# PongBoy.net
KiCad netlist of a schematic drawn in Altium Designer
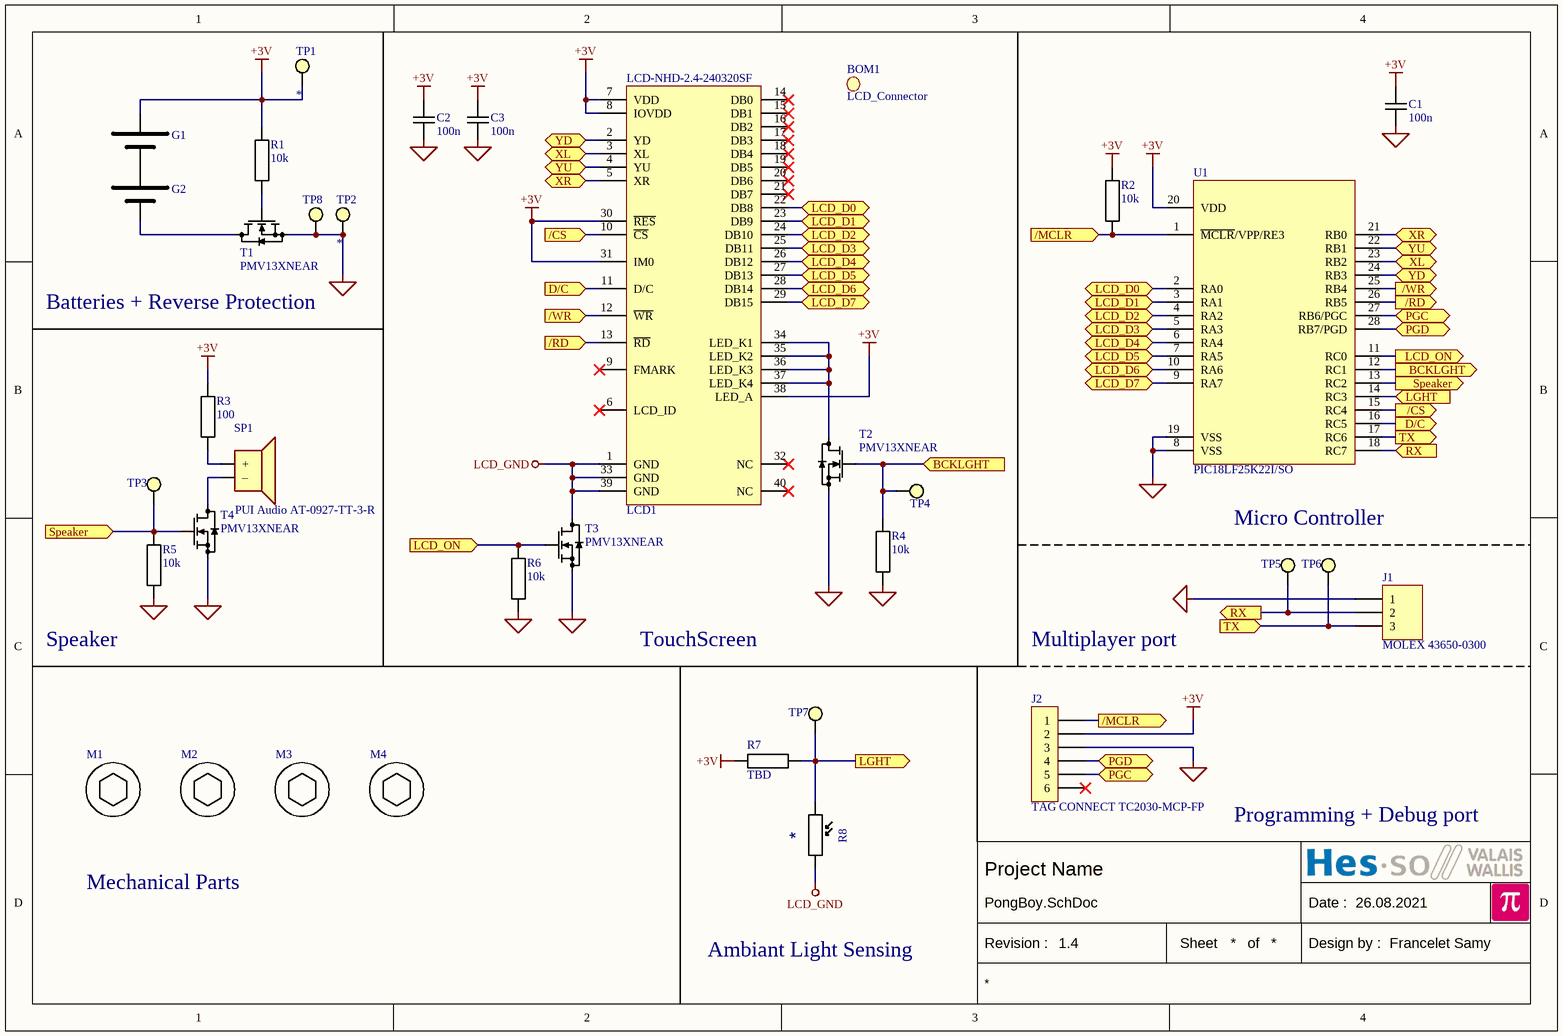
[diagram p0: PongBoy.SchDoc]

(export (version "E")
  (design (tool "Eeschema 10.0.6"))
  (components
    (comp (ref "BOM1")
      (value "LCD_Connector")
      (description "Component without pattern")
      (libsource (lib "altium-import") (part "root_0_Additional BOM Entry_"))
    )
    (comp (ref "C1")
      (value "100n")
      (footprint "CAPACITOR 2012 REFLOW")
      (description "Capacitor")
      (libsource (lib "altium-import") (part "root_1_Capacitor_"))
    )
    (comp (ref "C2")
      (value "100n")
      (footprint "CAPACITOR 2012 REFLOW")
      (description "Capacitor")
      (libsource (lib "altium-import") (part "root_1_Capacitor_"))
    )
    (comp (ref "C3")
      (value "100n")
      (footprint "CAPACITOR 2012 REFLOW")
      (description "Capacitor")
      (libsource (lib "altium-import") (part "root_1_Capacitor_"))
    )
    (comp (ref "G1")
      (value "AAA Battery Holder")
      (footprint "1.5V Cell AAA/LR03")
      (description "Battery Generic")
      (libsource (lib "altium-import") (part "root_0_Battery_"))
    )
    (comp (ref "G2")
      (value "AAA Battery Holder")
      (footprint "1.5V Cell AAA/LR03")
      (description "Battery Generic")
      (libsource (lib "altium-import") (part "root_0_Battery_"))
    )
    (comp (ref "J1")
      (value "MOLEX 43650-0300")
      (footprint "MOLEX 43650-0300")
      (description "Micro-Fit 3.0 Right-Angle Header, 3.00mm Pitch, Single Row, 3 Circuits")
      (libsource (lib "altium-import") (part "root_0_MOLEX 43650-0300_"))
    )
    (comp (ref "J2")
      (value "TAG CONNECT TC2030-MCP-FP")
      (footprint "TAG CONNECT TC2030-MCP-FP")
      (libsource (lib "altium-import") (part "root_0_mirrored_TAG CONNECT TC2030-MCP-FP_"))
    )
    (comp (ref "LCD1")
      (value "LCD-NHD-2.4-240320SF")
      (footprint "LCD-NHD-2.4-240320SF")
      (description "NEWHEAVEN LCD")
      (libsource (lib "altium-import") (part "root_0_LCD-NHD-2.4-240320SF_"))
    )
    (comp (ref "M1")
      (value "M3x20")
      (footprint "Screw Hex Socket M3X5 Unconnected")
      (description "Screw Hex Socket Unconnected BN610")
      (libsource (lib "altium-import") (part "root_0_Screw Hex Socket Unconnected_"))
    )
    (comp (ref "M2")
      (value "M3x20")
      (footprint "Screw Hex Socket M3X5 Unconnected")
      (description "Screw Hex Socket Unconnected BN610")
      (libsource (lib "altium-import") (part "root_0_Screw Hex Socket Unconnected_"))
    )
    (comp (ref "M3")
      (value "M3x20")
      (footprint "Screw Hex Socket M3X5 Unconnected")
      (description "Screw Hex Socket Unconnected BN610")
      (libsource (lib "altium-import") (part "root_0_Screw Hex Socket Unconnected_"))
    )
    (comp (ref "M4")
      (value "M3x20")
      (footprint "Screw Hex Socket M3X5 Unconnected")
      (description "Screw Hex Socket Unconnected BN610")
      (libsource (lib "altium-import") (part "root_0_Screw Hex Socket Unconnected_"))
    )
    (comp (ref "R1")
      (value "10k")
      (footprint "RESISTOR 2012 REFLOW")
      (description "Resistor")
      (libsource (lib "altium-import") (part "root_1_Resistor_"))
    )
    (comp (ref "R2")
      (value "10k")
      (footprint "RESISTOR 2012 REFLOW")
      (description "Resistor")
      (libsource (lib "altium-import") (part "root_1_Resistor_"))
    )
    (comp (ref "R3")
      (value "100")
      (footprint "RESISTOR 2012 REFLOW")
      (description "Resistor")
      (libsource (lib "altium-import") (part "root_1_Resistor_"))
    )
    (comp (ref "R4")
      (value "10k")
      (footprint "RESISTOR 2012 REFLOW")
      (description "Resistor")
      (libsource (lib "altium-import") (part "root_1_Resistor_"))
    )
    (comp (ref "R5")
      (value "10k")
      (footprint "RESISTOR 2012 REFLOW")
      (description "Resistor")
      (libsource (lib "altium-import") (part "root_1_Resistor_"))
    )
    (comp (ref "R6")
      (value "10k")
      (footprint "RESISTOR 2012 REFLOW")
      (description "Resistor")
      (libsource (lib "altium-import") (part "root_1_Resistor_"))
    )
    (comp (ref "R7")
      (value "TBD")
      (footprint "RESISTOR 2012 REFLOW")
      (description "Resistor")
      (libsource (lib "altium-import") (part "root_2_Resistor_"))
    )
    (comp (ref "R8")
      (value "*")
      (footprint "LDR VT900")
      (description "Light Dependent Resistor")
      (fields (field (name "ALTIUM_VALUE") "*"))
      (libsource (lib "altium-import") (part "root_3_LDR_"))
    )
    (comp (ref "SP1")
      (value "PUI Audio AT-0927-TT-3-R")
      (footprint "Speaker PUI Audio AT-0927-TT-3-R")
      (description "Speaker PUI Audio AT-0927-TT-3-R")
      (libsource (lib "altium-import") (part "root_0_Speaker PUI Audio AT-0927-TT-3-R_"))
    )
    (comp (ref "T1")
      (value "PMV13XNEAR")
      (footprint "SOT23 P0.95 C1.6x3.0 H1.3")
      (description "Generic MOS-N")
      (libsource (lib "altium-import") (part "root_3_mirrored_MOS-N SOT23 G-S-D_"))
    )
    (comp (ref "T2")
      (value "PMV13XNEAR")
      (footprint "SOT23 P0.95 C1.6x3.0 H1.3")
      (description "Generic MOS-N")
      (libsource (lib "altium-import") (part "root_0_mirrored_MOS-N SOT23 G-S-D_"))
    )
    (comp (ref "T3")
      (value "PMV13XNEAR")
      (footprint "SOT23 P0.95 C1.6x3.0 H1.3")
      (description "Generic MOS-N")
      (libsource (lib "altium-import") (part "root_0_MOS-N SOT23 G-S-D_"))
    )
    (comp (ref "T4")
      (value "PMV13XNEAR")
      (footprint "SOT23 P0.95 C1.6x3.0 H1.3")
      (description "Generic MOS-N")
      (libsource (lib "altium-import") (part "root_0_MOS-N SOT23 G-S-D_"))
    )
    (comp (ref "TP1")
      (value "*")
      (footprint "Pad D2.0")
      (description "Pad")
      (libsource (lib "altium-import") (part "root_0_Pad_"))
    )
    (comp (ref "TP2")
      (value "*")
      (footprint "Pad D2.0")
      (description "Pad")
      (libsource (lib "altium-import") (part "root_0_Pad_"))
    )
    (comp (ref "TP3")
      (value "*")
      (footprint "Test Point Vogt 1016L.68M")
      (description "Test Point")
      (libsource (lib "altium-import") (part "root_0_Test Point_"))
    )
    (comp (ref "TP4")
      (value "*")
      (footprint "Test Point Vogt 1016L.68M")
      (description "Test Point")
      (libsource (lib "altium-import") (part "root_3_Test Point_"))
    )
    (comp (ref "TP5")
      (value "*")
      (footprint "Test Point Vogt 1016L.68M")
      (description "Test Point")
      (libsource (lib "altium-import") (part "root_0_Test Point_"))
    )
    (comp (ref "TP6")
      (value "*")
      (footprint "Test Point Vogt 1016L.68M")
      (description "Test Point")
      (libsource (lib "altium-import") (part "root_0_Test Point_"))
    )
    (comp (ref "TP7")
      (value "*")
      (footprint "Test Point Vogt 1016L.68M")
      (description "Test Point")
      (libsource (lib "altium-import") (part "root_0_Test Point_"))
    )
    (comp (ref "TP8")
      (value "*")
      (footprint "Test Point Vogt 1016L.68M")
      (description "Test Point")
      (libsource (lib "altium-import") (part "root_0_Test Point_"))
    )
    (comp (ref "U1")
      (value "PIC18LF25K22I/SO")
      (footprint "SO28 P1.27 C7.5X17.9 H2.7")
      (description "Flash Microcontrollers  with 10-Bit A/D and nanoWatt Technology")
      (libsource (lib "altium-import") (part "root_0_PIC18F2_K22-_/SO_"))
    )
  )
  (nets
    (net (code "1") (name "+3V") (class "Default")
      (node (ref "C1") (pin "2") (pinfunction "2_2") (pintype "passive"))
      (node (ref "C2") (pin "2") (pinfunction "2_2") (pintype "passive"))
      (node (ref "C3") (pin "2") (pinfunction "2_2") (pintype "passive"))
      (node (ref "G1") (pin "1") (pinfunction "+_1") (pintype "passive"))
      (node (ref "J2") (pin "2") (pinfunction "2_2") (pintype "passive"))
      (node (ref "LCD1") (pin "30") (pinfunction "~{RES}_30") (pintype "passive"))
      (node (ref "LCD1") (pin "31") (pinfunction "IM0_31") (pintype "passive"))
      (node (ref "LCD1") (pin "38") (pinfunction "LED_A_38") (pintype "passive"))
      (node (ref "LCD1") (pin "7") (pinfunction "VDD_7") (pintype "passive"))
      (node (ref "LCD1") (pin "8") (pinfunction "IOVDD_8") (pintype "passive"))
      (node (ref "R1") (pin "2") (pinfunction "2_2") (pintype "passive"))
      (node (ref "R2") (pin "2") (pinfunction "2_2") (pintype "passive"))
      (node (ref "R3") (pin "2") (pinfunction "2_2") (pintype "passive"))
      (node (ref "R7") (pin "2") (pinfunction "2_2") (pintype "passive"))
      (node (ref "TP1") (pin "1") (pinfunction "1_1") (pintype "passive"))
      (node (ref "U1") (pin "20") (pinfunction "VDD_20") (pintype "passive"))
    )
    (net (code "2") (name "/BCKLGHT") (class "Default")
      (node (ref "R4") (pin "2") (pinfunction "2_2") (pintype "passive"))
      (node (ref "T2") (pin "1") (pinfunction "G_1") (pintype "passive"))
      (node (ref "TP4") (pin "1") (pinfunction "1_1") (pintype "passive"))
      (node (ref "U1") (pin "12") (pinfunction "RC1_12") (pintype "passive"))
    )
    (net (code "3") (name "/D{slash}C") (class "Default")
      (node (ref "LCD1") (pin "11") (pinfunction "D/C_11") (pintype "passive"))
      (node (ref "U1") (pin "16") (pinfunction "RC5_16") (pintype "passive"))
    )
    (net (code "4") (name "/LCD_D0") (class "Default")
      (node (ref "LCD1") (pin "22") (pinfunction "DB8_22") (pintype "passive"))
      (node (ref "U1") (pin "2") (pinfunction "RA0_2") (pintype "passive"))
    )
    (net (code "5") (name "/LCD_D1") (class "Default")
      (node (ref "LCD1") (pin "23") (pinfunction "DB9_23") (pintype "passive"))
      (node (ref "U1") (pin "3") (pinfunction "RA1_3") (pintype "passive"))
    )
    (net (code "6") (name "/LCD_D2") (class "Default")
      (node (ref "LCD1") (pin "24") (pinfunction "DB10_24") (pintype "passive"))
      (node (ref "U1") (pin "4") (pinfunction "RA2_4") (pintype "passive"))
    )
    (net (code "7") (name "/LCD_D3") (class "Default")
      (node (ref "LCD1") (pin "25") (pinfunction "DB11_25") (pintype "passive"))
      (node (ref "U1") (pin "5") (pinfunction "RA3_5") (pintype "passive"))
    )
    (net (code "8") (name "/LCD_D4") (class "Default")
      (node (ref "LCD1") (pin "26") (pinfunction "DB12_26") (pintype "passive"))
      (node (ref "U1") (pin "6") (pinfunction "RA4_6") (pintype "passive"))
    )
    (net (code "9") (name "/LCD_D5") (class "Default")
      (node (ref "LCD1") (pin "27") (pinfunction "DB13_27") (pintype "passive"))
      (node (ref "U1") (pin "7") (pinfunction "RA5_7") (pintype "passive"))
    )
    (net (code "10") (name "/LCD_D6") (class "Default")
      (node (ref "LCD1") (pin "28") (pinfunction "DB14_28") (pintype "passive"))
      (node (ref "U1") (pin "10") (pinfunction "RA6_10") (pintype "passive"))
    )
    (net (code "11") (name "/LCD_D7") (class "Default")
      (node (ref "LCD1") (pin "29") (pinfunction "DB15_29") (pintype "passive"))
      (node (ref "U1") (pin "9") (pinfunction "RA7_9") (pintype "passive"))
    )
    (net (code "12") (name "/LCD_ON") (class "Default")
      (node (ref "R6") (pin "2") (pinfunction "2_2") (pintype "passive"))
      (node (ref "T3") (pin "1") (pinfunction "G_1") (pintype "passive"))
      (node (ref "U1") (pin "11") (pinfunction "RC0_11") (pintype "passive"))
    )
    (net (code "13") (name "/LGHT") (class "Default")
      (node (ref "R7") (pin "1") (pinfunction "1_1") (pintype "passive"))
      (node (ref "R8") (pin "1") (pinfunction "1_1") (pintype "passive"))
      (node (ref "TP7") (pin "1") (pinfunction "1_1") (pintype "passive"))
      (node (ref "U1") (pin "14") (pinfunction "RC3_14") (pintype "passive"))
    )
    (net (code "14") (name "/PGC") (class "Default")
      (node (ref "J2") (pin "5") (pinfunction "5_5") (pintype "passive"))
      (node (ref "U1") (pin "27") (pinfunction "RB6/PGC_27") (pintype "passive"))
    )
    (net (code "15") (name "/PGD") (class "Default")
      (node (ref "J2") (pin "4") (pinfunction "4_4") (pintype "passive"))
      (node (ref "U1") (pin "28") (pinfunction "RB7/PGD_28") (pintype "passive"))
    )
    (net (code "16") (name "/RX") (class "Default")
      (node (ref "J1") (pin "2") (pinfunction "2_2") (pintype "passive"))
      (node (ref "TP5") (pin "1") (pinfunction "1_1") (pintype "passive"))
      (node (ref "U1") (pin "18") (pinfunction "RC7_18") (pintype "passive"))
    )
    (net (code "17") (name "/Speaker") (class "Default")
      (node (ref "R5") (pin "2") (pinfunction "2_2") (pintype "passive"))
      (node (ref "T4") (pin "1") (pinfunction "G_1") (pintype "passive"))
      (node (ref "TP3") (pin "1") (pinfunction "1_1") (pintype "passive"))
      (node (ref "U1") (pin "13") (pinfunction "RC2_13") (pintype "passive"))
    )
    (net (code "18") (name "/TX") (class "Default")
      (node (ref "J1") (pin "3") (pinfunction "3_3") (pintype "passive"))
      (node (ref "TP6") (pin "1") (pinfunction "1_1") (pintype "passive"))
      (node (ref "U1") (pin "17") (pinfunction "RC6_17") (pintype "passive"))
    )
    (net (code "19") (name "/XL") (class "Default")
      (node (ref "LCD1") (pin "3") (pinfunction "XL_3") (pintype "passive"))
      (node (ref "U1") (pin "23") (pinfunction "RB2_23") (pintype "passive"))
    )
    (net (code "20") (name "/XR") (class "Default")
      (node (ref "LCD1") (pin "5") (pinfunction "XR_5") (pintype "passive"))
      (node (ref "U1") (pin "21") (pinfunction "RB0_21") (pintype "passive"))
    )
    (net (code "21") (name "/YD") (class "Default")
      (node (ref "LCD1") (pin "2") (pinfunction "YD_2") (pintype "passive"))
      (node (ref "U1") (pin "24") (pinfunction "RB3_24") (pintype "passive"))
    )
    (net (code "22") (name "/YU") (class "Default")
      (node (ref "LCD1") (pin "4") (pinfunction "YU_4") (pintype "passive"))
      (node (ref "U1") (pin "22") (pinfunction "RB1_22") (pintype "passive"))
    )
    (net (code "23") (name "/{slash}CS") (class "Default")
      (node (ref "LCD1") (pin "10") (pinfunction "~{CS}_10") (pintype "passive"))
      (node (ref "U1") (pin "15") (pinfunction "RC4_15") (pintype "passive"))
    )
    (net (code "24") (name "/{slash}MCLR") (class "Default")
      (node (ref "J2") (pin "1") (pinfunction "1_1") (pintype "passive"))
      (node (ref "R2") (pin "1") (pinfunction "1_1") (pintype "passive"))
      (node (ref "U1") (pin "1") (pinfunction "~{MCLR}/VPP/RE3_1") (pintype "passive"))
    )
    (net (code "25") (name "/{slash}RD") (class "Default")
      (node (ref "LCD1") (pin "13") (pinfunction "~{RD}_13") (pintype "passive"))
      (node (ref "U1") (pin "26") (pinfunction "RB5_26") (pintype "passive"))
    )
    (net (code "26") (name "/{slash}WR") (class "Default")
      (node (ref "LCD1") (pin "12") (pinfunction "~{WR}_12") (pintype "passive"))
      (node (ref "U1") (pin "25") (pinfunction "RB4_25") (pintype "passive"))
    )
    (net (code "27") (name "GND") (class "Default")
      (node (ref "C1") (pin "1") (pinfunction "1_1") (pintype "passive"))
      (node (ref "C2") (pin "1") (pinfunction "1_1") (pintype "passive"))
      (node (ref "C3") (pin "1") (pinfunction "1_1") (pintype "passive"))
      (node (ref "J1") (pin "1") (pinfunction "1_1") (pintype "passive"))
      (node (ref "J2") (pin "3") (pinfunction "3_3") (pintype "passive"))
      (node (ref "R4") (pin "1") (pinfunction "1_1") (pintype "passive"))
      (node (ref "R5") (pin "1") (pinfunction "1_1") (pintype "passive"))
      (node (ref "R6") (pin "1") (pinfunction "1_1") (pintype "passive"))
      (node (ref "T1") (pin "2") (pinfunction "S_2") (pintype "passive"))
      (node (ref "T2") (pin "2") (pinfunction "S_2") (pintype "passive"))
      (node (ref "T3") (pin "2") (pinfunction "S_2") (pintype "passive"))
      (node (ref "T4") (pin "2") (pinfunction "S_2") (pintype "passive"))
      (node (ref "TP2") (pin "1") (pinfunction "1_1") (pintype "passive"))
      (node (ref "TP8") (pin "1") (pinfunction "1_1") (pintype "passive"))
      (node (ref "U1") (pin "19") (pinfunction "VSS_19") (pintype "passive"))
      (node (ref "U1") (pin "8") (pinfunction "VSS_8") (pintype "passive"))
    )
    (net (code "28") (name "LCD_GND") (class "Default")
      (node (ref "LCD1") (pin "1") (pinfunction "GND_1") (pintype "passive"))
      (node (ref "LCD1") (pin "33") (pinfunction "GND_33") (pintype "passive"))
      (node (ref "LCD1") (pin "39") (pinfunction "GND_39") (pintype "passive"))
      (node (ref "R8") (pin "2") (pinfunction "2_2") (pintype "passive"))
      (node (ref "T3") (pin "3") (pinfunction "D_3") (pintype "passive"))
    )
    (net (code "29") (name "Net-(G1-—)") (class "Default")
      (node (ref "G1") (pin "2") (pinfunction "—_2") (pintype "passive"))
      (node (ref "G2") (pin "1") (pinfunction "+_1") (pintype "passive"))
    )
    (net (code "30") (name "Net-(G2-—)") (class "Default")
      (node (ref "G2") (pin "2") (pinfunction "—_2") (pintype "passive"))
      (node (ref "T1") (pin "3") (pinfunction "D_3") (pintype "passive"))
    )
    (net (code "31") (name "Net-(LCD1-LED_K1)") (class "Default")
      (node (ref "LCD1") (pin "34") (pinfunction "LED_K1_34") (pintype "passive"))
      (node (ref "LCD1") (pin "35") (pinfunction "LED_K2_35") (pintype "passive"))
      (node (ref "LCD1") (pin "36") (pinfunction "LED_K3_36") (pintype "passive"))
      (node (ref "LCD1") (pin "37") (pinfunction "LED_K4_37") (pintype "passive"))
      (node (ref "T2") (pin "3") (pinfunction "D_3") (pintype "passive"))
    )
    (net (code "32") (name "Net-(SP1-+)") (class "Default")
      (node (ref "R3") (pin "1") (pinfunction "1_1") (pintype "passive"))
      (node (ref "SP1") (pin "1") (pinfunction "+_1") (pintype "passive"))
    )
    (net (code "33") (name "Net-(SP1-–)") (class "Default")
      (node (ref "SP1") (pin "2") (pinfunction "–_2") (pintype "passive"))
      (node (ref "T4") (pin "3") (pinfunction "D_3") (pintype "passive"))
    )
    (net (code "34") (name "Net-(T1-G)") (class "Default")
      (node (ref "R1") (pin "1") (pinfunction "1_1") (pintype "passive"))
      (node (ref "T1") (pin "1") (pinfunction "G_1") (pintype "passive"))
    )
    (net (code "35") (name "unconnected-(J2-Pad6)") (class "Default")
      (node (ref "J2") (pin "6") (pinfunction "6_6") (pintype "passive+no_connect"))
    )
    (net (code "36") (name "unconnected-(LCD1-DB0-Pad14)") (class "Default")
      (node (ref "LCD1") (pin "14") (pinfunction "DB0_14") (pintype "passive+no_connect"))
    )
    (net (code "37") (name "unconnected-(LCD1-DB1-Pad15)") (class "Default")
      (node (ref "LCD1") (pin "15") (pinfunction "DB1_15") (pintype "passive+no_connect"))
    )
    (net (code "38") (name "unconnected-(LCD1-DB2-Pad16)") (class "Default")
      (node (ref "LCD1") (pin "16") (pinfunction "DB2_16") (pintype "passive+no_connect"))
    )
    (net (code "39") (name "unconnected-(LCD1-DB3-Pad17)") (class "Default")
      (node (ref "LCD1") (pin "17") (pinfunction "DB3_17") (pintype "passive+no_connect"))
    )
    (net (code "40") (name "unconnected-(LCD1-DB4-Pad18)") (class "Default")
      (node (ref "LCD1") (pin "18") (pinfunction "DB4_18") (pintype "passive+no_connect"))
    )
    (net (code "41") (name "unconnected-(LCD1-DB5-Pad19)") (class "Default")
      (node (ref "LCD1") (pin "19") (pinfunction "DB5_19") (pintype "passive+no_connect"))
    )
    (net (code "42") (name "unconnected-(LCD1-DB6-Pad20)") (class "Default")
      (node (ref "LCD1") (pin "20") (pinfunction "DB6_20") (pintype "passive+no_connect"))
    )
    (net (code "43") (name "unconnected-(LCD1-DB7-Pad21)") (class "Default")
      (node (ref "LCD1") (pin "21") (pinfunction "DB7_21") (pintype "passive+no_connect"))
    )
    (net (code "44") (name "unconnected-(LCD1-FMARK-Pad9)") (class "Default")
      (node (ref "LCD1") (pin "9") (pinfunction "FMARK_9") (pintype "passive+no_connect"))
    )
    (net (code "45") (name "unconnected-(LCD1-LCD_ID-Pad6)") (class "Default")
      (node (ref "LCD1") (pin "6") (pinfunction "LCD_ID_6") (pintype "passive+no_connect"))
    )
    (net (code "46") (name "unconnected-(LCD1-NC-Pad32)") (class "Default")
      (node (ref "LCD1") (pin "32") (pinfunction "NC_32") (pintype "passive+no_connect"))
    )
    (net (code "47") (name "unconnected-(LCD1-NC-Pad40)") (class "Default")
      (node (ref "LCD1") (pin "40") (pinfunction "NC_40") (pintype "passive+no_connect"))
    )
  )
)
